# Controlador_Digital.net
KiCad netlist of a schematic drawn in Altium Designer
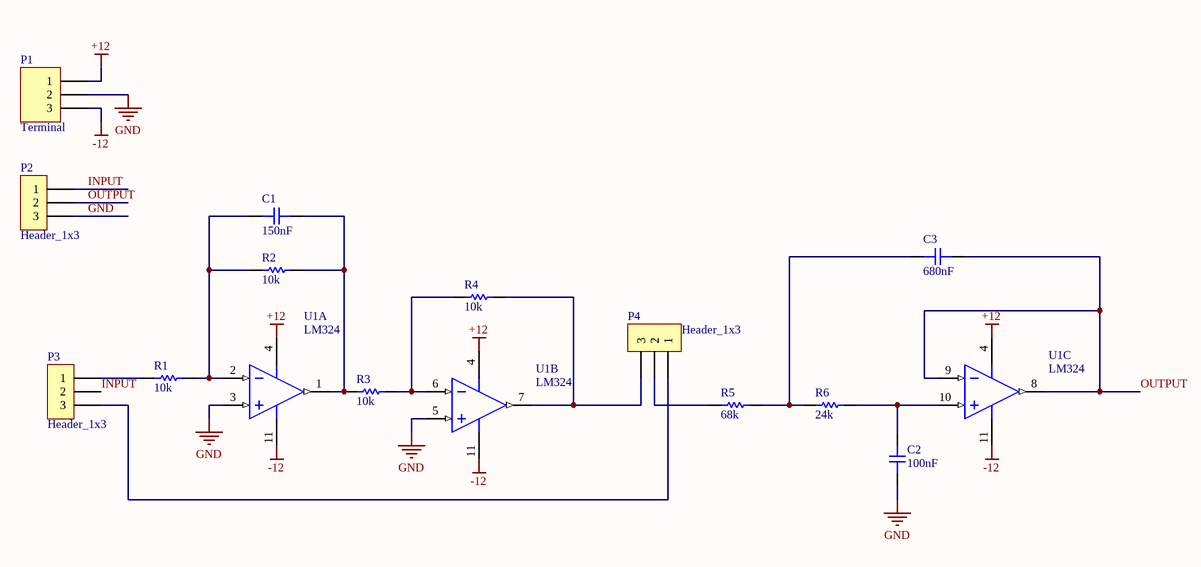
[diagram p0: Controlador_Digital.SchDoc]

(export (version "E")
  (design (tool "Eeschema 10.0.6"))
  (components
    (comp (ref "C1")
      (value "150nF")
      (footprint "C200-350-150")
      (description "Capacitor")
      (fields (field (name "VOLTAGE") "100 V") (field (name "PUBLISHER") "Altium Limited"))
      (libsource (lib "GPDSE") (part "Capacitor"))
    )
    (comp (ref "C2")
      (value "100nF")
      (footprint "C300-450-150")
      (description "Capacitor")
      (fields (field (name "VOLTAGE") "100 V") (field (name "PUBLISHER") "Altium Limited"))
      (libsource (lib "GPDSE") (part "Capacitor"))
    )
    (comp (ref "C3")
      (value "680nF")
      (footprint "C400-550-150")
      (description "Capacitor")
      (fields (field (name "VOLTAGE") "100 V") (field (name "PUBLISHER") "Altium Limited"))
      (libsource (lib "GPDSE") (part "Capacitor"))
    )
    (comp (ref "P1")
      (value "Terminal")
      (footprint "KRE_3")
      (description "Terminal Block 1x3")
      (libsource (lib "GPDSE") (part "KRE_3"))
    )
    (comp (ref "P2")
      (value "Header_1x3")
      (footprint "HDR-M-1x3-2.54mm-180-9.2mm")
      (description "Header, 1 Line, 3 Columns, 3 Pins")
      (fields (field (name "PUBLISHER") "Altium Limited"))
      (libsource (lib "GPDSE") (part "Header_1x3"))
    )
    (comp (ref "P3")
      (value "Header_1x3")
      (footprint "HDR-M-1x3-2.54mm-180-9.2mm")
      (description "Header, 1 Line, 3 Columns, 3 Pins")
      (fields (field (name "PUBLISHER") "Altium Limited"))
      (libsource (lib "GPDSE") (part "Header_1x3"))
    )
    (comp (ref "P4")
      (value "Header_1x3")
      (footprint "HDR-M-1x3-2.54mm-180-9.2mm")
      (description "Header, 1 Line, 3 Columns, 3 Pins")
      (fields (field (name "PUBLISHER") "Altium Limited"))
      (libsource (lib "") (part "Header_1x3_1"))
    )
    (comp (ref "R1")
      (value "10k")
      (footprint "R400-2.0mm")
      (description "Resistor")
      (fields
        (field (name "TOLERANCE") "5%")
        (field (name "POWER") "1/4 W")
        (field (name "PUBLISHER") "Altium Limited")
      )
      (libsource (lib "GPDSE") (part "Resistor"))
    )
    (comp (ref "R2")
      (value "10k")
      (footprint "R400-2.0mm")
      (description "Resistor")
      (fields
        (field (name "TOLERANCE") "5%")
        (field (name "POWER") "1/4 W")
        (field (name "PUBLISHER") "Altium Limited")
      )
      (libsource (lib "GPDSE") (part "Resistor"))
    )
    (comp (ref "R3")
      (value "10k")
      (footprint "R400-2.0mm")
      (description "Resistor")
      (fields
        (field (name "TOLERANCE") "5%")
        (field (name "POWER") "1/4 W")
        (field (name "PUBLISHER") "Altium Limited")
      )
      (libsource (lib "GPDSE") (part "Resistor"))
    )
    (comp (ref "R4")
      (value "10k")
      (footprint "R400-2.0mm")
      (description "Resistor")
      (fields
        (field (name "TOLERANCE") "5%")
        (field (name "POWER") "1/4 W")
        (field (name "PUBLISHER") "Altium Limited")
      )
      (libsource (lib "GPDSE") (part "Resistor"))
    )
    (comp (ref "R5")
      (value "68k")
      (footprint "R400-2.0mm")
      (description "Resistor")
      (fields
        (field (name "TOLERANCE") "5%")
        (field (name "POWER") "1/4 W")
        (field (name "PUBLISHER") "Altium Limited")
      )
      (libsource (lib "GPDSE") (part "Resistor"))
    )
    (comp (ref "R6")
      (value "24k")
      (footprint "R400-2.0mm")
      (description "Resistor")
      (fields
        (field (name "TOLERANCE") "5%")
        (field (name "POWER") "1/4 W")
        (field (name "PUBLISHER") "Altium Limited")
      )
      (libsource (lib "GPDSE") (part "Resistor"))
    )
    (comp (ref "U1")
      (value "LM324")
      (footprint "TI-N14")
      (libsource (lib "Controlador_Digital") (part "LM324"))
    )
  )
  (nets
    (net (code "1") (name "+12") (class "Default")
      (node (ref "P1") (pin "1") (pinfunction "1_1") (pintype "passive"))
      (node (ref "U1") (pin "4") (pinfunction "VCC+_4") (pintype "power_in"))
    )
    (net (code "2") (name "-12") (class "Default")
      (node (ref "P1") (pin "3") (pinfunction "3_3") (pintype "passive"))
      (node (ref "U1") (pin "11") (pinfunction "VCC-_11") (pintype "power_in"))
    )
    (net (code "3") (name "/INPUT") (class "Default")
      (node (ref "P2") (pin "1") (pinfunction "1_1") (pintype "passive"))
      (node (ref "P3") (pin "2") (pinfunction "2_2") (pintype "passive"))
    )
    (net (code "4") (name "/OUTPUT") (class "Default")
      (node (ref "C3") (pin "1") (pinfunction "1_1") (pintype "passive"))
      (node (ref "P2") (pin "2") (pinfunction "2_2") (pintype "passive"))
      (node (ref "U1") (pin "8") (pinfunction "OUT1_8") (pintype "output"))
      (node (ref "U1") (pin "9") (pinfunction "IN1-_9") (pintype "input"))
    )
    (net (code "5") (name "GND") (class "Default")
      (node (ref "C2") (pin "1") (pinfunction "1_1") (pintype "passive"))
      (node (ref "P1") (pin "2") (pinfunction "2_2") (pintype "passive"))
      (node (ref "P2") (pin "3") (pinfunction "3_3") (pintype "passive"))
      (node (ref "U1") (pin "3") (pinfunction "IN1+_3") (pintype "input"))
      (node (ref "U1") (pin "5") (pinfunction "IN1+_5") (pintype "input"))
    )
    (net (code "6") (name "Net-(C3-Pad2)") (class "Default")
      (node (ref "C3") (pin "2") (pinfunction "2_2") (pintype "passive"))
      (node (ref "R5") (pin "2") (pinfunction "2_2") (pintype "passive"))
      (node (ref "R6") (pin "1") (pinfunction "1_1") (pintype "passive"))
    )
    (net (code "7") (name "Net-(P3-Pad1)") (class "Default")
      (node (ref "P3") (pin "1") (pinfunction "1_1") (pintype "passive"))
      (node (ref "R1") (pin "1") (pinfunction "1_1") (pintype "passive"))
    )
    (net (code "8") (name "Net-(P3-Pad3)") (class "Default")
      (node (ref "P3") (pin "3") (pinfunction "3_3") (pintype "passive"))
      (node (ref "P4") (pin "1") (pinfunction "1_1") (pintype "passive"))
    )
    (net (code "9") (name "Net-(P4-Pad2)") (class "Default")
      (node (ref "P4") (pin "2") (pinfunction "2_2") (pintype "passive"))
      (node (ref "R5") (pin "1") (pinfunction "1_1") (pintype "passive"))
    )
    (net (code "10") (name "Net-(U1A-IN1-)") (class "Default")
      (node (ref "C1") (pin "2") (pinfunction "2_2") (pintype "passive"))
      (node (ref "R1") (pin "2") (pinfunction "2_2") (pintype "passive"))
      (node (ref "R2") (pin "1") (pinfunction "1_1") (pintype "passive"))
      (node (ref "U1") (pin "2") (pinfunction "IN1-_2") (pintype "input"))
    )
    (net (code "11") (name "Net-(U1A-OUT1)") (class "Default")
      (node (ref "C1") (pin "1") (pinfunction "1_1") (pintype "passive"))
      (node (ref "R2") (pin "2") (pinfunction "2_2") (pintype "passive"))
      (node (ref "R3") (pin "1") (pinfunction "1_1") (pintype "passive"))
      (node (ref "U1") (pin "1") (pinfunction "OUT1_1") (pintype "output"))
    )
    (net (code "12") (name "Net-(U1B-IN1-)") (class "Default")
      (node (ref "R3") (pin "2") (pinfunction "2_2") (pintype "passive"))
      (node (ref "R4") (pin "1") (pinfunction "1_1") (pintype "passive"))
      (node (ref "U1") (pin "6") (pinfunction "IN1-_6") (pintype "input"))
    )
    (net (code "13") (name "Net-(U1B-OUT1)") (class "Default")
      (node (ref "P4") (pin "3") (pinfunction "3_3") (pintype "passive"))
      (node (ref "R4") (pin "2") (pinfunction "2_2") (pintype "passive"))
      (node (ref "U1") (pin "7") (pinfunction "OUT1_7") (pintype "output"))
    )
    (net (code "14") (name "Net-(U1C-IN1+)") (class "Default")
      (node (ref "C2") (pin "2") (pinfunction "2_2") (pintype "passive"))
      (node (ref "R6") (pin "2") (pinfunction "2_2") (pintype "passive"))
      (node (ref "U1") (pin "10") (pinfunction "IN1+_10") (pintype "input"))
    )
  )
)
